# SCH_Macros-Keyboard_2024-05-12.net
KiCad netlist of a schematic drawn in EasyEDA
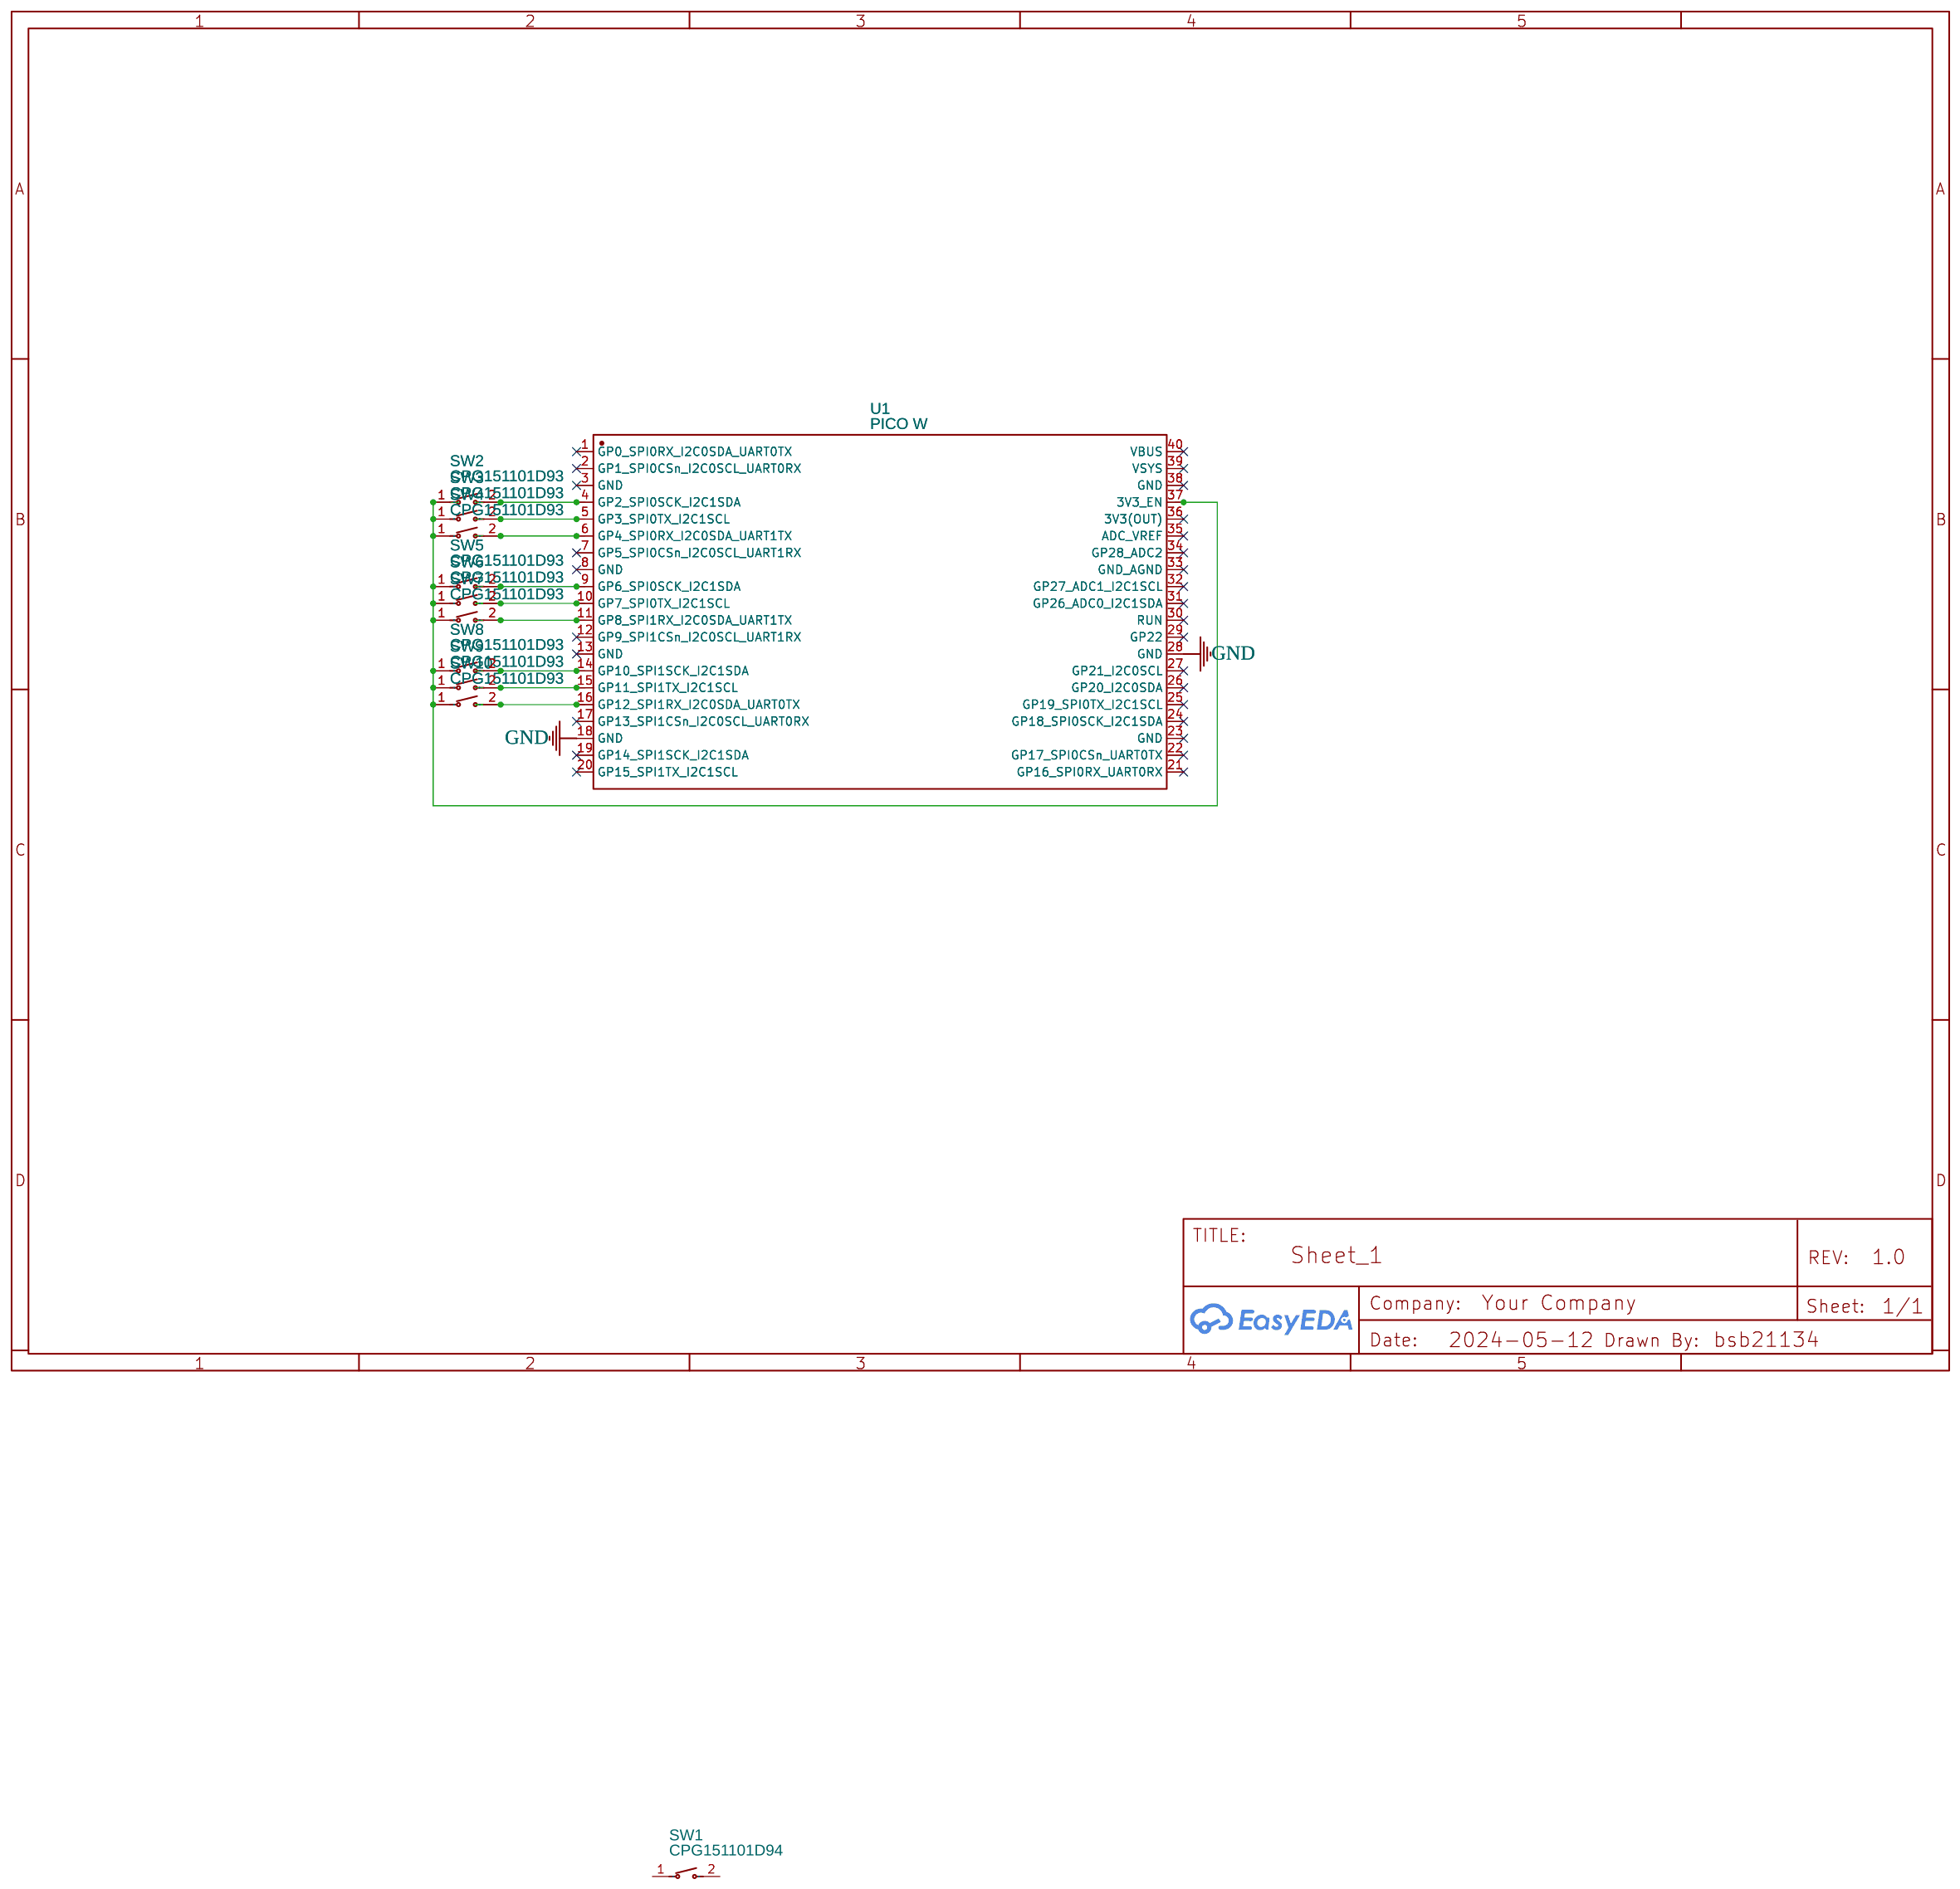
[diagram p0: schematic sheet]

(export (version "E")
  (design (tool "Eeschema 10.0.6"))
  (components
    (comp (ref "SW1")
      (value "CPG151101D94")
      (fields (field (name "Manufacturer") "Kailh(凯华)"))
      (libsource (lib "") (part "CPG151101D94"))
    )
    (comp (ref "SW2")
      (value "CPG151101D93")
      (fields (field (name "Manufacturer") "Kailh(凯华)"))
      (libsource (lib "") (part "CPG151101D93"))
    )
    (comp (ref "SW3")
      (value "CPG151101D93")
      (fields (field (name "Manufacturer") "Kailh(凯华)"))
      (libsource (lib "") (part "CPG151101D93"))
    )
    (comp (ref "SW4")
      (value "CPG151101D93")
      (fields (field (name "Manufacturer") "Kailh(凯华)"))
      (libsource (lib "") (part "CPG151101D93"))
    )
    (comp (ref "SW5")
      (value "CPG151101D93")
      (fields (field (name "Manufacturer") "Kailh(凯华)"))
      (libsource (lib "") (part "CPG151101D93"))
    )
    (comp (ref "SW6")
      (value "CPG151101D93")
      (fields (field (name "Manufacturer") "Kailh(凯华)"))
      (libsource (lib "") (part "CPG151101D93"))
    )
    (comp (ref "SW7")
      (value "CPG151101D93")
      (fields (field (name "Manufacturer") "Kailh(凯华)"))
      (libsource (lib "") (part "CPG151101D93"))
    )
    (comp (ref "SW8")
      (value "CPG151101D93")
      (fields (field (name "Manufacturer") "Kailh(凯华)"))
      (libsource (lib "") (part "CPG151101D93"))
    )
    (comp (ref "SW9")
      (value "CPG151101D93")
      (fields (field (name "Manufacturer") "Kailh(凯华)"))
      (libsource (lib "") (part "CPG151101D93"))
    )
    (comp (ref "SW10")
      (value "CPG151101D93")
      (fields (field (name "Manufacturer") "Kailh(凯华)"))
      (libsource (lib "") (part "CPG151101D93"))
    )
    (comp (ref "U1")
      (value "PICO W")
      (fields (field (name "Manufacturer") "Raspberry Pi(树莓派)"))
      (libsource (lib "") (part "PICO W"))
    )
  )
  (nets
    (net (code "1") (name "GND") (class "Default")
      (node (ref "U1") (pin "18") (pinfunction "GND_18") (pintype "unspecified"))
      (node (ref "U1") (pin "28") (pinfunction "GND_28") (pintype "unspecified"))
    )
    (net (code "2") (name "Net-(U1-3V3_EN)") (class "Default")
      (node (ref "SW10") (pin "1") (pinfunction "1_1") (pintype "unspecified"))
      (node (ref "SW2") (pin "1") (pinfunction "1_1") (pintype "unspecified"))
      (node (ref "SW3") (pin "1") (pinfunction "1_1") (pintype "unspecified"))
      (node (ref "SW4") (pin "1") (pinfunction "1_1") (pintype "unspecified"))
      (node (ref "SW5") (pin "1") (pinfunction "1_1") (pintype "unspecified"))
      (node (ref "SW6") (pin "1") (pinfunction "1_1") (pintype "unspecified"))
      (node (ref "SW7") (pin "1") (pinfunction "1_1") (pintype "unspecified"))
      (node (ref "SW8") (pin "1") (pinfunction "1_1") (pintype "unspecified"))
      (node (ref "SW9") (pin "1") (pinfunction "1_1") (pintype "unspecified"))
      (node (ref "U1") (pin "37") (pinfunction "3V3_EN_37") (pintype "unspecified"))
    )
    (net (code "3") (name "Net-(U1-GP2_SPI0SCK_I2C1SDA)") (class "Default")
      (node (ref "SW2") (pin "2") (pinfunction "2_2") (pintype "unspecified"))
      (node (ref "U1") (pin "4") (pinfunction "GP2_SPI0SCK_I2C1SDA_4") (pintype "unspecified"))
    )
    (net (code "4") (name "Net-(U1-GP3_SPI0TX_I2C1SCL)") (class "Default")
      (node (ref "SW3") (pin "2") (pinfunction "2_2") (pintype "unspecified"))
      (node (ref "U1") (pin "5") (pinfunction "GP3_SPI0TX_I2C1SCL_5") (pintype "unspecified"))
    )
    (net (code "5") (name "Net-(U1-GP4_SPI0RX_I2C0SDA_UART1TX)") (class "Default")
      (node (ref "SW4") (pin "2") (pinfunction "2_2") (pintype "unspecified"))
      (node (ref "U1") (pin "6") (pinfunction "GP4_SPI0RX_I2C0SDA_UART1TX_6") (pintype "unspecified"))
    )
    (net (code "6") (name "Net-(U1-GP6_SPI0SCK_I2C1SDA)") (class "Default")
      (node (ref "SW5") (pin "2") (pinfunction "2_2") (pintype "unspecified"))
      (node (ref "U1") (pin "9") (pinfunction "GP6_SPI0SCK_I2C1SDA_9") (pintype "unspecified"))
    )
    (net (code "7") (name "Net-(U1-GP7_SPI0TX_I2C1SCL)") (class "Default")
      (node (ref "SW6") (pin "2") (pinfunction "2_2") (pintype "unspecified"))
      (node (ref "U1") (pin "10") (pinfunction "GP7_SPI0TX_I2C1SCL_10") (pintype "unspecified"))
    )
    (net (code "8") (name "Net-(U1-GP8_SPI1RX_I2C0SDA_UART1TX)") (class "Default")
      (node (ref "SW7") (pin "2") (pinfunction "2_2") (pintype "unspecified"))
      (node (ref "U1") (pin "11") (pinfunction "GP8_SPI1RX_I2C0SDA_UART1TX_11") (pintype "unspecified"))
    )
    (net (code "9") (name "Net-(U1-GP10_SPI1SCK_I2C1SDA)") (class "Default")
      (node (ref "SW8") (pin "2") (pinfunction "2_2") (pintype "unspecified"))
      (node (ref "U1") (pin "14") (pinfunction "GP10_SPI1SCK_I2C1SDA_14") (pintype "unspecified"))
    )
    (net (code "10") (name "Net-(U1-GP11_SPI1TX_I2C1SCL)") (class "Default")
      (node (ref "SW9") (pin "2") (pinfunction "2_2") (pintype "unspecified"))
      (node (ref "U1") (pin "15") (pinfunction "GP11_SPI1TX_I2C1SCL_15") (pintype "unspecified"))
    )
    (net (code "11") (name "Net-(U1-GP12_SPI1RX_I2C0SDA_UART0TX)") (class "Default")
      (node (ref "SW10") (pin "2") (pinfunction "2_2") (pintype "unspecified"))
      (node (ref "U1") (pin "16") (pinfunction "GP12_SPI1RX_I2C0SDA_UART0TX_16") (pintype "unspecified"))
    )
    (net (code "12") (name "unconnected-(SW1-Pad1)") (class "Default")
      (node (ref "SW1") (pin "1") (pinfunction "1_1") (pintype "unspecified"))
    )
    (net (code "13") (name "unconnected-(SW1-Pad2)") (class "Default")
      (node (ref "SW1") (pin "2") (pinfunction "2_2") (pintype "unspecified"))
    )
    (net (code "14") (name "unconnected-(U1-3V3(OUT)-Pad36)") (class "Default")
      (node (ref "U1") (pin "36") (pinfunction "3V3(OUT)_36") (pintype "unspecified+no_connect"))
    )
    (net (code "15") (name "unconnected-(U1-ADC_VREF-Pad35)") (class "Default")
      (node (ref "U1") (pin "35") (pinfunction "ADC_VREF_35") (pintype "unspecified+no_connect"))
    )
    (net (code "16") (name "unconnected-(U1-GND-Pad3)") (class "Default")
      (node (ref "U1") (pin "3") (pinfunction "GND_3") (pintype "unspecified+no_connect"))
    )
    (net (code "17") (name "unconnected-(U1-GND-Pad8)") (class "Default")
      (node (ref "U1") (pin "8") (pinfunction "GND_8") (pintype "unspecified+no_connect"))
    )
    (net (code "18") (name "unconnected-(U1-GND-Pad13)") (class "Default")
      (node (ref "U1") (pin "13") (pinfunction "GND_13") (pintype "unspecified+no_connect"))
    )
    (net (code "19") (name "unconnected-(U1-GND-Pad23)") (class "Default")
      (node (ref "U1") (pin "23") (pinfunction "GND_23") (pintype "unspecified+no_connect"))
    )
    (net (code "20") (name "unconnected-(U1-GND-Pad38)") (class "Default")
      (node (ref "U1") (pin "38") (pinfunction "GND_38") (pintype "unspecified+no_connect"))
    )
    (net (code "21") (name "unconnected-(U1-GND_AGND-Pad33)") (class "Default")
      (node (ref "U1") (pin "33") (pinfunction "GND_AGND_33") (pintype "unspecified+no_connect"))
    )
    (net (code "22") (name "unconnected-(U1-GP0_SPI0RX_I2C0SDA_UART0TX-Pad1)") (class "Default")
      (node (ref "U1") (pin "1") (pinfunction "GP0_SPI0RX_I2C0SDA_UART0TX_1") (pintype "unspecified+no_connect"))
    )
    (net (code "23") (name "unconnected-(U1-GP1_SPI0CSn_I2C0SCL_UART0RX-Pad2)") (class "Default")
      (node (ref "U1") (pin "2") (pinfunction "GP1_SPI0CSn_I2C0SCL_UART0RX_2") (pintype "unspecified+no_connect"))
    )
    (net (code "24") (name "unconnected-(U1-GP5_SPI0CSn_I2C0SCL_UART1RX-Pad7)") (class "Default")
      (node (ref "U1") (pin "7") (pinfunction "GP5_SPI0CSn_I2C0SCL_UART1RX_7") (pintype "unspecified+no_connect"))
    )
    (net (code "25") (name "unconnected-(U1-GP9_SPI1CSn_I2C0SCL_UART1RX-Pad12)") (class "Default")
      (node (ref "U1") (pin "12") (pinfunction "GP9_SPI1CSn_I2C0SCL_UART1RX_12") (pintype "unspecified+no_connect"))
    )
    (net (code "26") (name "unconnected-(U1-GP13_SPI1CSn_I2C0SCL_UART0RX-Pad17)") (class "Default")
      (node (ref "U1") (pin "17") (pinfunction "GP13_SPI1CSn_I2C0SCL_UART0RX_17") (pintype "unspecified+no_connect"))
    )
    (net (code "27") (name "unconnected-(U1-GP14_SPI1SCK_I2C1SDA-Pad19)") (class "Default")
      (node (ref "U1") (pin "19") (pinfunction "GP14_SPI1SCK_I2C1SDA_19") (pintype "unspecified+no_connect"))
    )
    (net (code "28") (name "unconnected-(U1-GP15_SPI1TX_I2C1SCL-Pad20)") (class "Default")
      (node (ref "U1") (pin "20") (pinfunction "GP15_SPI1TX_I2C1SCL_20") (pintype "unspecified+no_connect"))
    )
    (net (code "29") (name "unconnected-(U1-GP16_SPI0RX_UART0RX-Pad21)") (class "Default")
      (node (ref "U1") (pin "21") (pinfunction "GP16_SPI0RX_UART0RX_21") (pintype "unspecified+no_connect"))
    )
    (net (code "30") (name "unconnected-(U1-GP17_SPI0CSn_UART0TX-Pad22)") (class "Default")
      (node (ref "U1") (pin "22") (pinfunction "GP17_SPI0CSn_UART0TX_22") (pintype "unspecified+no_connect"))
    )
    (net (code "31") (name "unconnected-(U1-GP18_SPI0SCK_I2C1SDA-Pad24)") (class "Default")
      (node (ref "U1") (pin "24") (pinfunction "GP18_SPI0SCK_I2C1SDA_24") (pintype "unspecified+no_connect"))
    )
    (net (code "32") (name "unconnected-(U1-GP19_SPI0TX_I2C1SCL-Pad25)") (class "Default")
      (node (ref "U1") (pin "25") (pinfunction "GP19_SPI0TX_I2C1SCL_25") (pintype "unspecified+no_connect"))
    )
    (net (code "33") (name "unconnected-(U1-GP20_I2C0SDA-Pad26)") (class "Default")
      (node (ref "U1") (pin "26") (pinfunction "GP20_I2C0SDA_26") (pintype "unspecified+no_connect"))
    )
    (net (code "34") (name "unconnected-(U1-GP21_I2C0SCL-Pad27)") (class "Default")
      (node (ref "U1") (pin "27") (pinfunction "GP21_I2C0SCL_27") (pintype "unspecified+no_connect"))
    )
    (net (code "35") (name "unconnected-(U1-GP22-Pad29)") (class "Default")
      (node (ref "U1") (pin "29") (pinfunction "GP22_29") (pintype "unspecified+no_connect"))
    )
    (net (code "36") (name "unconnected-(U1-GP26_ADC0_I2C1SDA-Pad31)") (class "Default")
      (node (ref "U1") (pin "31") (pinfunction "GP26_ADC0_I2C1SDA_31") (pintype "unspecified+no_connect"))
    )
    (net (code "37") (name "unconnected-(U1-GP27_ADC1_I2C1SCL-Pad32)") (class "Default")
      (node (ref "U1") (pin "32") (pinfunction "GP27_ADC1_I2C1SCL_32") (pintype "unspecified+no_connect"))
    )
    (net (code "38") (name "unconnected-(U1-GP28_ADC2-Pad34)") (class "Default")
      (node (ref "U1") (pin "34") (pinfunction "GP28_ADC2_34") (pintype "unspecified+no_connect"))
    )
    (net (code "39") (name "unconnected-(U1-RUN-Pad30)") (class "Default")
      (node (ref "U1") (pin "30") (pinfunction "RUN_30") (pintype "unspecified+no_connect"))
    )
    (net (code "40") (name "unconnected-(U1-VBUS-Pad40)") (class "Default")
      (node (ref "U1") (pin "40") (pinfunction "VBUS_40") (pintype "unspecified+no_connect"))
    )
    (net (code "41") (name "unconnected-(U1-VSYS-Pad39)") (class "Default")
      (node (ref "U1") (pin "39") (pinfunction "VSYS_39") (pintype "unspecified+no_connect"))
    )
  )
)
